# epapertagjig.net
KiCad netlist of a schematic drawn in EAGLE
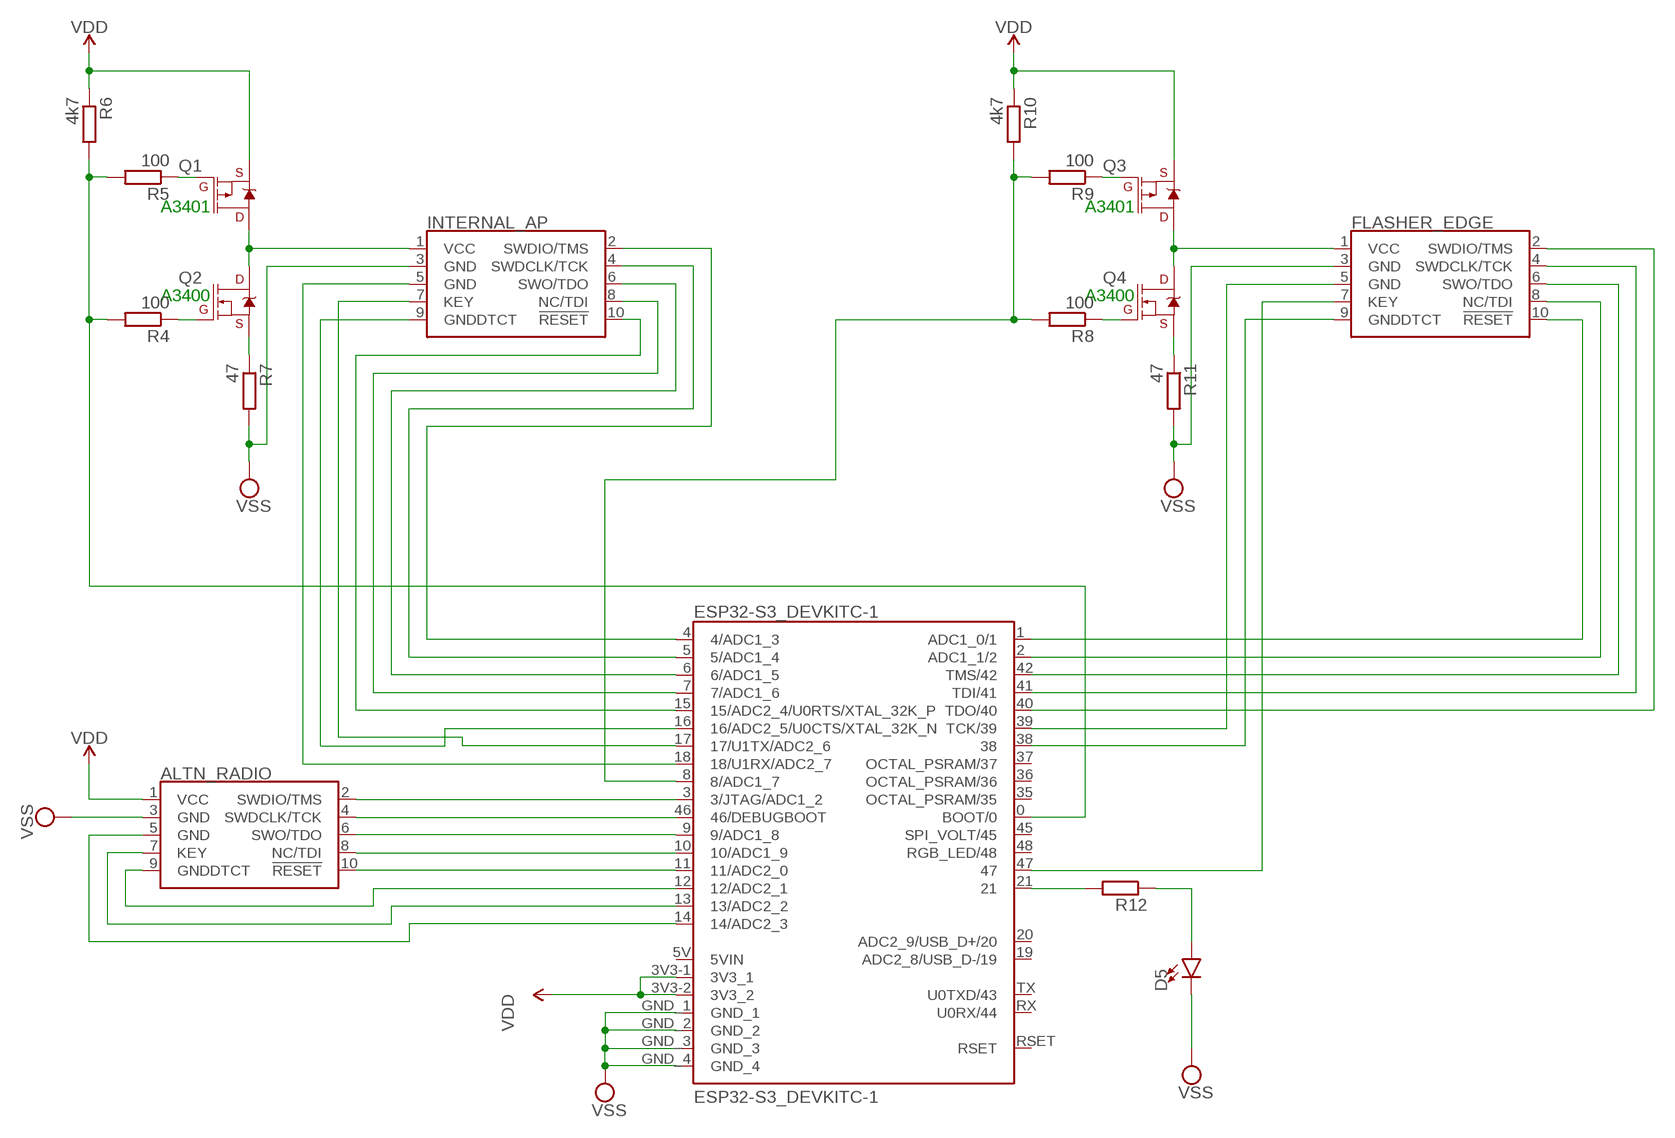
[diagram p0: schematic, sheet 1]
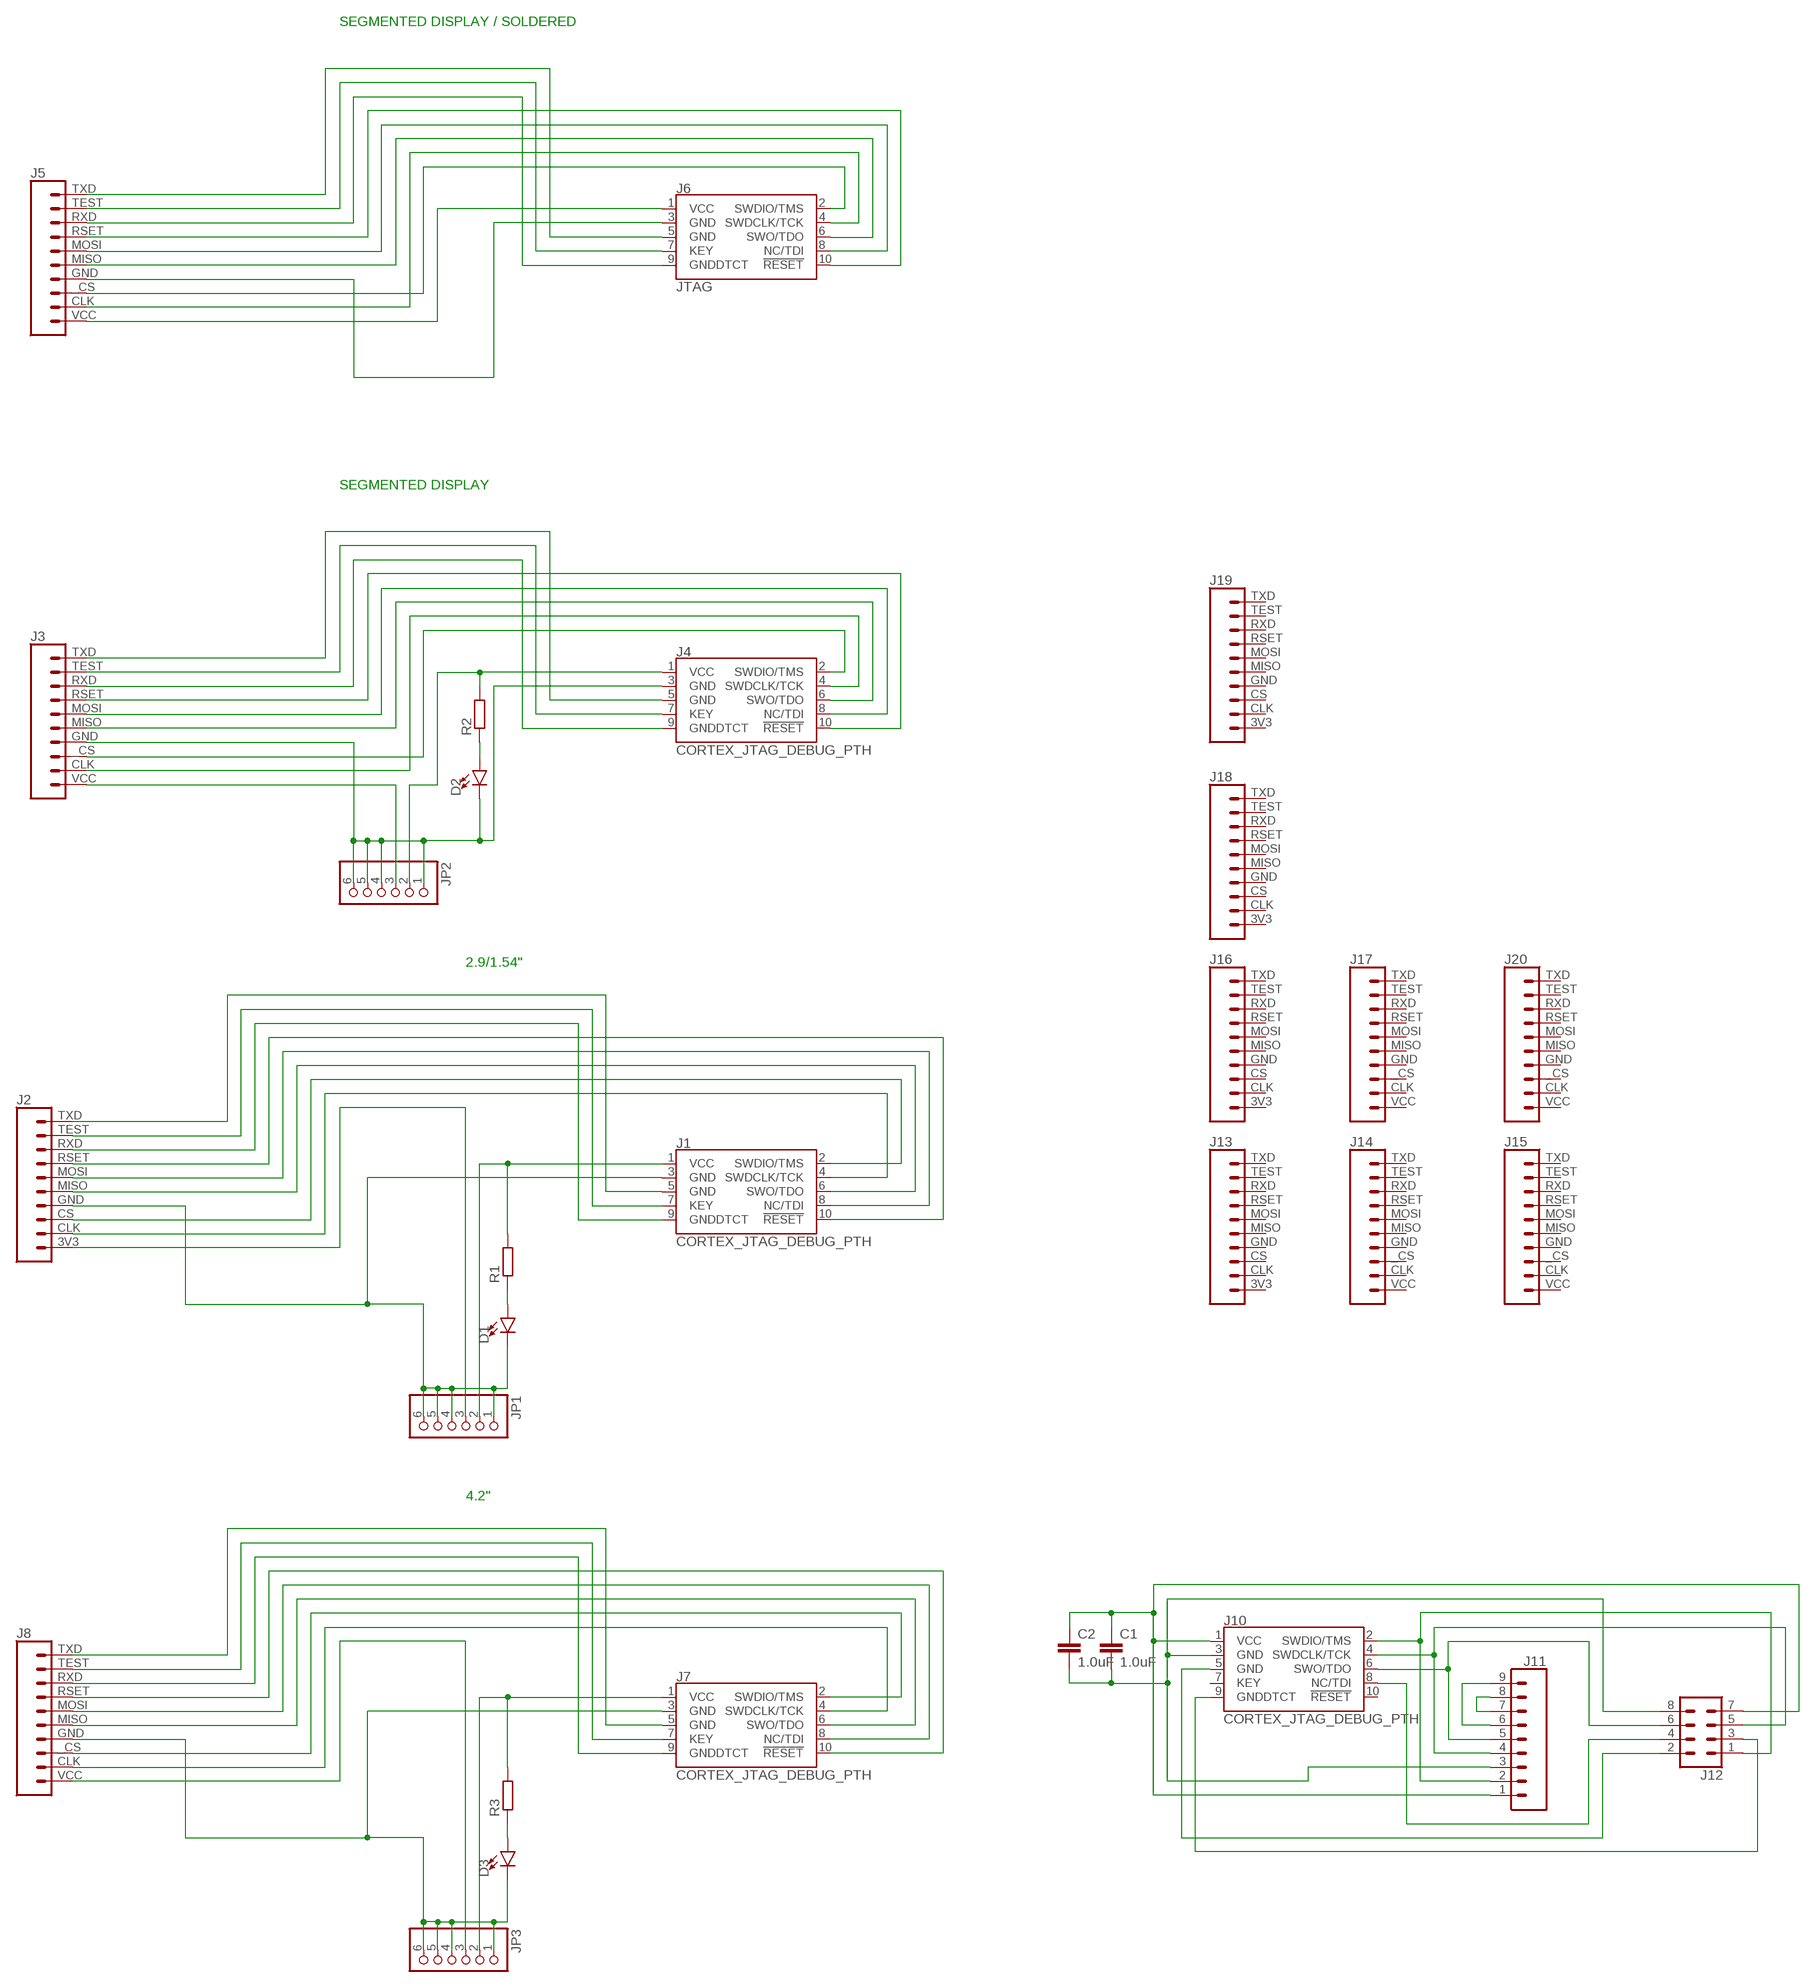
[diagram p1: schematic, sheet 2]

(export (version "E")
  (design (tool "Eeschema 10.0.6"))
  (components
    (comp (ref "C1")
      (value "1.0uF")
      (footprint "eagle-import:1206")
      (libsource (lib "eagle-import") (part "1.0UF-1206-50V-10%"))
    )
    (comp (ref "C2")
      (value "1.0uF")
      (footprint "eagle-import:1206")
      (libsource (lib "eagle-import") (part "1.0UF-1206-50V-10%"))
    )
    (comp (ref "D1")
      (value "LED1206")
      (footprint "eagle-import:LED-1206")
      (libsource (lib "eagle-import") (part "LED1206"))
    )
    (comp (ref "D2")
      (value "LED1206")
      (footprint "eagle-import:LED-1206")
      (libsource (lib "eagle-import") (part "LED1206"))
    )
    (comp (ref "D3")
      (value "LED1206")
      (footprint "eagle-import:LED-1206")
      (libsource (lib "eagle-import") (part "LED1206"))
    )
    (comp (ref "J1")
      (value "CORTEX_JTAG_DEBUG_PTH")
      (footprint "eagle-import:2X5-PTH-1.27MM")
      (libsource (lib "eagle-import") (part "CORTEX_JTAG_DEBUG_PTH"))
    )
    (comp (ref "J2")
      (value "SOLUM_ZBS_DEBUG")
      (footprint "eagle-import:SOLUM_ZBS_DEBUG")
      (libsource (lib "eagle-import") (part "SOLUM_ZBS_DEBUG"))
    )
    (comp (ref "J3")
      (value "SOLUM_ZBS_DEBUGSEGMENTED_DISPLAY")
      (footprint "eagle-import:SOLUM_ZBS_DEBUG_SEG")
      (libsource (lib "eagle-import") (part "SOLUM_ZBS_DEBUGSEGMENTED_DISPLAY"))
    )
    (comp (ref "J4")
      (value "CORTEX_JTAG_DEBUG_PTH")
      (footprint "eagle-import:2X5-PTH-1.27MM")
      (libsource (lib "eagle-import") (part "CORTEX_JTAG_DEBUG_PTH"))
    )
    (comp (ref "J5")
      (value "SOLUM_ZBS_DEBUGSEGMENTED_DISPLAY")
      (footprint "eagle-import:SOLUM_ZBS_DEBUG_SEG")
      (libsource (lib "eagle-import") (part "SOLUM_ZBS_DEBUGSEGMENTED_DISPLAY"))
    )
    (comp (ref "J6")
      (value "JTAG")
      (footprint "eagle-import:2X5-SMD-1.27MM")
      (libsource (lib "eagle-import") (part "CORTEX_JTAG_DEBUG_SMD"))
    )
    (comp (ref "J7")
      (value "CORTEX_JTAG_DEBUG_PTH")
      (footprint "eagle-import:2X5-PTH-1.27MM")
      (libsource (lib "eagle-import") (part "CORTEX_JTAG_DEBUG_PTH"))
    )
    (comp (ref "J8")
      (value "SOLUM_ZBS_DEBUGSOLUM_ZBS_DEBUG_4.2")
      (footprint "eagle-import:SOLUM_ZBS_DEBUG_4.2")
      (libsource (lib "eagle-import") (part "SOLUM_ZBS_DEBUGSOLUM_ZBS_DEBUG_4.2"))
    )
    (comp (ref "J10")
      (value "CORTEX_JTAG_DEBUG_PTH")
      (footprint "eagle-import:2X5-PTH-1.27MM")
      (libsource (lib "eagle-import") (part "CORTEX_JTAG_DEBUG_PTH"))
    )
    (comp (ref "J11")
      (value "CONN_09")
      (footprint "eagle-import:1X09")
      (libsource (lib "eagle-import") (part "CONN_09"))
    )
    (comp (ref "J12")
      (value "CONN_04X2")
      (footprint "eagle-import:2X4")
      (libsource (lib "eagle-import") (part "CONN_04X2"))
    )
    (comp (ref "J13")
      (value "SOLUM_ZBS_DEBUG")
      (footprint "eagle-import:SOLUM_ZBS_DEBUG")
      (libsource (lib "eagle-import") (part "SOLUM_ZBS_DEBUG"))
    )
    (comp (ref "J14")
      (value "SOLUM_ZBS_DEBUGSEGMENTED_DISPLAY")
      (footprint "eagle-import:SOLUM_ZBS_DEBUG_SEG")
      (libsource (lib "eagle-import") (part "SOLUM_ZBS_DEBUGSEGMENTED_DISPLAY"))
    )
    (comp (ref "J15")
      (value "SOLUM_ZBS_DEBUGSOLUM_ZBS_DEBUG_4.2")
      (footprint "eagle-import:SOLUM_ZBS_DEBUG_4.2")
      (libsource (lib "eagle-import") (part "SOLUM_ZBS_DEBUGSOLUM_ZBS_DEBUG_4.2"))
    )
    (comp (ref "J16")
      (value "SOLUM_ZBS_DEBUG")
      (footprint "eagle-import:SOLUM_ZBS_DEBUG")
      (libsource (lib "eagle-import") (part "SOLUM_ZBS_DEBUG"))
    )
    (comp (ref "J17")
      (value "SOLUM_ZBS_DEBUGSEGMENTED_DISPLAY")
      (footprint "eagle-import:SOLUM_ZBS_DEBUG_SEG")
      (libsource (lib "eagle-import") (part "SOLUM_ZBS_DEBUGSEGMENTED_DISPLAY"))
    )
    (comp (ref "J18")
      (value "SOLUM_ZBS_DEBUG")
      (footprint "eagle-import:SOLUM_ZBS_DEBUG")
      (libsource (lib "eagle-import") (part "SOLUM_ZBS_DEBUG"))
    )
    (comp (ref "J19")
      (value "SOLUM_ZBS_DEBUG")
      (footprint "eagle-import:SOLUM_ZBS_DEBUG")
      (libsource (lib "eagle-import") (part "SOLUM_ZBS_DEBUG"))
    )
    (comp (ref "J20")
      (value "SOLUM_ZBS_DEBUGSOLUM_ZBS_DEBUG_4.2")
      (footprint "eagle-import:SOLUM_ZBS_DEBUG_4.2")
      (libsource (lib "eagle-import") (part "SOLUM_ZBS_DEBUGSOLUM_ZBS_DEBUG_4.2"))
    )
    (comp (ref "JP1")
      (value "PINHD-1X6/90")
      (footprint "eagle-import:1X06_90")
      (libsource (lib "eagle-import") (part "PINHD-1X6/90"))
    )
    (comp (ref "JP2")
      (value "PINHD-1X6/90")
      (footprint "eagle-import:1X06_90")
      (libsource (lib "eagle-import") (part "PINHD-1X6/90"))
    )
    (comp (ref "JP3")
      (value "PINHD-1X6/90")
      (footprint "eagle-import:1X06_90")
      (libsource (lib "eagle-import") (part "PINHD-1X6/90"))
    )
    (comp (ref "R1")
      (value "R-EU_R1206")
      (footprint "eagle-import:R1206")
      (libsource (lib "eagle-import") (part "R-EU_R1206"))
    )
    (comp (ref "R2")
      (value "R-EU_R1206")
      (footprint "eagle-import:R1206")
      (libsource (lib "eagle-import") (part "R-EU_R1206"))
    )
    (comp (ref "R3")
      (value "R-EU_R1206")
      (footprint "eagle-import:R1206")
      (libsource (lib "eagle-import") (part "R-EU_R1206"))
    )
    (comp (ref "ALTN_RADIO")
      (value "JTAG")
      (footprint "eagle-import:2X5-SMD-1.27MM")
      (libsource (lib "eagle-import") (part "CORTEX_JTAG_DEBUG_SMD"))
    )
    (comp (ref "D5")
      (value "LED1206")
      (footprint "eagle-import:LED-1206")
      (libsource (lib "eagle-import") (part "LED1206"))
    )
    (comp (ref "FLASHER_EDGE")
      (value "CORTEX_JTAG_DEBUG_PTH")
      (footprint "eagle-import:2X5-PTH-1.27MM")
      (libsource (lib "eagle-import") (part "CORTEX_JTAG_DEBUG_PTH"))
    )
    (comp (ref "INTERNAL_AP")
      (value "JTAG")
      (footprint "eagle-import:2X5-SMD-1.27MM")
      (libsource (lib "eagle-import") (part "CORTEX_JTAG_DEBUG_SMD"))
    )
    (comp (ref "J9")
      (value "ESP32-S3_DEVKITC-1")
      (footprint "eagle-import:ESP32-S3_DEVKITC-1")
      (libsource (lib "eagle-import") (part "ESP32-S3_DEVKITC-1"))
    )
    (comp (ref "Q1")
      (value "1.1A/60V/600mΩ")
      (footprint "eagle-import:SOT23-3")
      (libsource (lib "eagle-import") (part "MOSFET_PCH-SI2309DS"))
    )
    (comp (ref "Q2")
      (value "5.8A/30V/35mΩ")
      (footprint "eagle-import:SOT23-3")
      (libsource (lib "eagle-import") (part "MOSFET-NCH-AO3404A"))
    )
    (comp (ref "Q3")
      (value "1.1A/60V/600mΩ")
      (footprint "eagle-import:SOT23-3")
      (libsource (lib "eagle-import") (part "MOSFET_PCH-SI2309DS"))
    )
    (comp (ref "Q4")
      (value "5.8A/30V/35mΩ")
      (footprint "eagle-import:SOT23-3")
      (libsource (lib "eagle-import") (part "MOSFET-NCH-AO3404A"))
    )
    (comp (ref "R4")
      (value "100")
      (footprint "eagle-import:R1206")
      (libsource (lib "eagle-import") (part "R-EU_R1206"))
    )
    (comp (ref "R5")
      (value "100")
      (footprint "eagle-import:R1206")
      (libsource (lib "eagle-import") (part "R-EU_R1206"))
    )
    (comp (ref "R6")
      (value "4k7")
      (footprint "eagle-import:R1206")
      (libsource (lib "eagle-import") (part "R-EU_R1206"))
    )
    (comp (ref "R7")
      (value "47")
      (footprint "eagle-import:R1206")
      (libsource (lib "eagle-import") (part "R-EU_R1206"))
    )
    (comp (ref "R8")
      (value "100")
      (footprint "eagle-import:R1206")
      (libsource (lib "eagle-import") (part "R-EU_R1206"))
    )
    (comp (ref "R9")
      (value "100")
      (footprint "eagle-import:R1206")
      (libsource (lib "eagle-import") (part "R-EU_R1206"))
    )
    (comp (ref "R10")
      (value "4k7")
      (footprint "eagle-import:R1206")
      (libsource (lib "eagle-import") (part "R-EU_R1206"))
    )
    (comp (ref "R11")
      (value "47")
      (footprint "eagle-import:R1206")
      (libsource (lib "eagle-import") (part "R-EU_R1206"))
    )
    (comp (ref "R12")
      (value "R-EU_R1206")
      (footprint "eagle-import:R1206")
      (libsource (lib "eagle-import") (part "R-EU_R1206"))
    )
  )
  (nets
    (net (code "1") (name "Net-(ALTN_RADIO-GNDDTCT)") (class "Default")
      (node (ref "ALTN_RADIO") (pin "9") (pinfunction "GNDDTCT_9") (pintype "bidirectional"))
      (node (ref "J9") (pin "12") (pinfunction "12/ADC2_1_12") (pintype "bidirectional"))
    )
    (net (code "2") (name "Net-(ALTN_RADIO-KEY)") (class "Default")
      (node (ref "ALTN_RADIO") (pin "7") (pinfunction "KEY_7") (pintype "bidirectional"))
      (node (ref "J9") (pin "13") (pinfunction "13/ADC2_2_13") (pintype "bidirectional"))
    )
    (net (code "3") (name "Net-(ALTN_RADIO-NC{slash}TDI)") (class "Default")
      (node (ref "ALTN_RADIO") (pin "8") (pinfunction "NC/TDI_8") (pintype "bidirectional"))
      (node (ref "J9") (pin "10") (pinfunction "10/ADC1_9_10") (pintype "bidirectional"))
    )
    (net (code "4") (name "Net-(ALTN_RADIO-SWDCLK{slash}TCK)") (class "Default")
      (node (ref "ALTN_RADIO") (pin "4") (pinfunction "SWDCLK/TCK_4") (pintype "bidirectional"))
      (node (ref "J9") (pin "46") (pinfunction "46/DEBUGBOOT_46") (pintype "bidirectional"))
    )
    (net (code "5") (name "Net-(ALTN_RADIO-SWDIO{slash}TMS)") (class "Default")
      (node (ref "ALTN_RADIO") (pin "2") (pinfunction "SWDIO/TMS_2") (pintype "bidirectional"))
      (node (ref "J9") (pin "3") (pinfunction "3/JTAG/ADC1_2_3") (pintype "bidirectional"))
    )
    (net (code "6") (name "Net-(ALTN_RADIO-SWO{slash}TDO)") (class "Default")
      (node (ref "ALTN_RADIO") (pin "6") (pinfunction "SWO/TDO_6") (pintype "bidirectional"))
      (node (ref "J9") (pin "9") (pinfunction "9/ADC1_8_9") (pintype "bidirectional"))
    )
    (net (code "7") (name "Net-(ALTN_RADIO-~{RESET})") (class "Default")
      (node (ref "ALTN_RADIO") (pin "10") (pinfunction "~{RESET}_10") (pintype "bidirectional"))
      (node (ref "J9") (pin "11") (pinfunction "11/ADC2_0_11") (pintype "bidirectional"))
    )
    (net (code "8") (name "Net-(C1-Pad2)") (class "Default")
      (node (ref "C1") (pin "2") (pinfunction "2_2") (pintype "passive"))
      (node (ref "C2") (pin "2") (pinfunction "2_2") (pintype "passive"))
      (node (ref "J10") (pin "3") (pinfunction "GND_3") (pintype "bidirectional"))
      (node (ref "J11") (pin "3") (pinfunction "3_3") (pintype "passive"))
      (node (ref "J12") (pin "8") (pinfunction "8_8") (pintype "passive"))
    )
    (net (code "9") (name "Net-(D1-PadA)") (class "Default")
      (node (ref "D1") (pin "A") (pinfunction "A_A") (pintype "passive"))
      (node (ref "R1") (pin "1") (pinfunction "1_1") (pintype "passive"))
    )
    (net (code "10") (name "Net-(D2-PadA)") (class "Default")
      (node (ref "D2") (pin "A") (pinfunction "A_A") (pintype "passive"))
      (node (ref "R2") (pin "1") (pinfunction "1_1") (pintype "passive"))
    )
    (net (code "11") (name "Net-(D3-PadA)") (class "Default")
      (node (ref "D3") (pin "A") (pinfunction "A_A") (pintype "passive"))
      (node (ref "R3") (pin "1") (pinfunction "1_1") (pintype "passive"))
    )
    (net (code "12") (name "Net-(D5-PadA)") (class "Default")
      (node (ref "D5") (pin "A") (pinfunction "A_A") (pintype "passive"))
      (node (ref "R12") (pin "1") (pinfunction "1_1") (pintype "passive"))
    )
    (net (code "13") (name "Net-(FLASHER_EDGE-GNDDTCT)") (class "Default")
      (node (ref "FLASHER_EDGE") (pin "9") (pinfunction "GNDDTCT_9") (pintype "bidirectional"))
      (node (ref "J9") (pin "38") (pinfunction "38_38") (pintype "bidirectional"))
    )
    (net (code "14") (name "Net-(FLASHER_EDGE-KEY)") (class "Default")
      (node (ref "FLASHER_EDGE") (pin "7") (pinfunction "KEY_7") (pintype "bidirectional"))
      (node (ref "J9") (pin "47") (pinfunction "47_47") (pintype "bidirectional"))
    )
    (net (code "15") (name "Net-(FLASHER_EDGE-NC{slash}TDI)") (class "Default")
      (node (ref "FLASHER_EDGE") (pin "8") (pinfunction "NC/TDI_8") (pintype "bidirectional"))
      (node (ref "J9") (pin "2") (pinfunction "ADC1_1/2_2") (pintype "bidirectional"))
    )
    (net (code "16") (name "Net-(FLASHER_EDGE-SWDCLK{slash}TCK)") (class "Default")
      (node (ref "FLASHER_EDGE") (pin "4") (pinfunction "SWDCLK/TCK_4") (pintype "bidirectional"))
      (node (ref "J9") (pin "41") (pinfunction "TDI/41_41") (pintype "bidirectional"))
    )
    (net (code "17") (name "Net-(FLASHER_EDGE-SWDIO{slash}TMS)") (class "Default")
      (node (ref "FLASHER_EDGE") (pin "2") (pinfunction "SWDIO/TMS_2") (pintype "bidirectional"))
      (node (ref "J9") (pin "40") (pinfunction "TDO/40_40") (pintype "bidirectional"))
    )
    (net (code "18") (name "Net-(FLASHER_EDGE-SWO{slash}TDO)") (class "Default")
      (node (ref "FLASHER_EDGE") (pin "6") (pinfunction "SWO/TDO_6") (pintype "bidirectional"))
      (node (ref "J9") (pin "42") (pinfunction "TMS/42_42") (pintype "bidirectional"))
    )
    (net (code "19") (name "Net-(FLASHER_EDGE-VCC)") (class "Default")
      (node (ref "FLASHER_EDGE") (pin "1") (pinfunction "VCC_1") (pintype "bidirectional"))
      (node (ref "Q3") (pin "3") (pinfunction "D_3") (pintype "bidirectional"))
      (node (ref "Q4") (pin "3") (pinfunction "D_3") (pintype "bidirectional"))
    )
    (net (code "20") (name "Net-(FLASHER_EDGE-~{RESET})") (class "Default")
      (node (ref "FLASHER_EDGE") (pin "10") (pinfunction "~{RESET}_10") (pintype "bidirectional"))
      (node (ref "J9") (pin "1") (pinfunction "ADC1_0/1_1") (pintype "bidirectional"))
    )
    (net (code "21") (name "Net-(INTERNAL_AP-GNDDTCT)") (class "Default")
      (node (ref "INTERNAL_AP") (pin "9") (pinfunction "GNDDTCT_9") (pintype "bidirectional"))
      (node (ref "J9") (pin "16") (pinfunction "16/ADC2_5/U0CTS/XTAL_32K_N_16") (pintype "bidirectional"))
    )
    (net (code "22") (name "Net-(INTERNAL_AP-KEY)") (class "Default")
      (node (ref "INTERNAL_AP") (pin "7") (pinfunction "KEY_7") (pintype "bidirectional"))
      (node (ref "J9") (pin "17") (pinfunction "17/U1TX/ADC2_6_17") (pintype "bidirectional"))
    )
    (net (code "23") (name "Net-(INTERNAL_AP-NC{slash}TDI)") (class "Default")
      (node (ref "INTERNAL_AP") (pin "8") (pinfunction "NC/TDI_8") (pintype "bidirectional"))
      (node (ref "J9") (pin "7") (pinfunction "7/ADC1_6_7") (pintype "bidirectional"))
    )
    (net (code "24") (name "Net-(INTERNAL_AP-SWDCLK{slash}TCK)") (class "Default")
      (node (ref "INTERNAL_AP") (pin "4") (pinfunction "SWDCLK/TCK_4") (pintype "bidirectional"))
      (node (ref "J9") (pin "5") (pinfunction "5/ADC1_4_5") (pintype "bidirectional"))
    )
    (net (code "25") (name "Net-(INTERNAL_AP-SWDIO{slash}TMS)") (class "Default")
      (node (ref "INTERNAL_AP") (pin "2") (pinfunction "SWDIO/TMS_2") (pintype "bidirectional"))
      (node (ref "J9") (pin "4") (pinfunction "4/ADC1_3_4") (pintype "bidirectional"))
    )
    (net (code "26") (name "Net-(INTERNAL_AP-SWO{slash}TDO)") (class "Default")
      (node (ref "INTERNAL_AP") (pin "6") (pinfunction "SWO/TDO_6") (pintype "bidirectional"))
      (node (ref "J9") (pin "6") (pinfunction "6/ADC1_5_6") (pintype "bidirectional"))
    )
    (net (code "27") (name "Net-(INTERNAL_AP-VCC)") (class "Default")
      (node (ref "INTERNAL_AP") (pin "1") (pinfunction "VCC_1") (pintype "bidirectional"))
      (node (ref "Q1") (pin "3") (pinfunction "D_3") (pintype "bidirectional"))
      (node (ref "Q2") (pin "3") (pinfunction "D_3") (pintype "bidirectional"))
    )
    (net (code "28") (name "Net-(INTERNAL_AP-~{RESET})") (class "Default")
      (node (ref "INTERNAL_AP") (pin "10") (pinfunction "~{RESET}_10") (pintype "bidirectional"))
      (node (ref "J9") (pin "15") (pinfunction "15/ADC2_4/U0RTS/XTAL_32K_P_15") (pintype "bidirectional"))
    )
    (net (code "29") (name "Net-(J1-GNDDTCT)") (class "Default")
      (node (ref "J1") (pin "9") (pinfunction "GNDDTCT_9") (pintype "bidirectional"))
      (node (ref "J2") (pin "RXD") (pinfunction "8_RXD") (pintype "passive"))
    )
    (net (code "30") (name "Net-(J1-KEY)") (class "Default")
      (node (ref "J1") (pin "7") (pinfunction "KEY_7") (pintype "bidirectional"))
      (node (ref "J2") (pin "TEST") (pinfunction "9_TEST") (pintype "passive"))
    )
    (net (code "31") (name "Net-(J1-NC{slash}TDI)") (class "Default")
      (node (ref "J1") (pin "8") (pinfunction "NC/TDI_8") (pintype "bidirectional"))
      (node (ref "J2") (pin "MOSI") (pinfunction "6_MOSI") (pintype "passive"))
    )
    (net (code "32") (name "Net-(J1-SWDCLK{slash}TCK)") (class "Default")
      (node (ref "J1") (pin "4") (pinfunction "SWDCLK/TCK_4") (pintype "bidirectional"))
      (node (ref "J2") (pin "CLK") (pinfunction "2_CLK") (pintype "passive"))
    )
    (net (code "33") (name "Net-(J1-SWDIO{slash}TMS)") (class "Default")
      (node (ref "J1") (pin "2") (pinfunction "SWDIO/TMS_2") (pintype "bidirectional"))
      (node (ref "J2") (pin "CS") (pinfunction "3_CS") (pintype "passive"))
    )
    (net (code "34") (name "Net-(J1-SWO{slash}TDO)") (class "Default")
      (node (ref "J1") (pin "6") (pinfunction "SWO/TDO_6") (pintype "bidirectional"))
      (node (ref "J2") (pin "MISO") (pinfunction "5_MISO") (pintype "passive"))
    )
    (net (code "35") (name "Net-(J1-VCC)") (class "Default")
      (node (ref "J1") (pin "1") (pinfunction "VCC_1") (pintype "bidirectional"))
      (node (ref "JP1") (pin "2") (pinfunction "2_2") (pintype "passive"))
      (node (ref "R1") (pin "2") (pinfunction "2_2") (pintype "passive"))
    )
    (net (code "36") (name "Net-(J1-~{RESET})") (class "Default")
      (node (ref "J1") (pin "10") (pinfunction "~{RESET}_10") (pintype "bidirectional"))
      (node (ref "J2") (pin "RSET") (pinfunction "7_RSET") (pintype "passive"))
    )
    (net (code "37") (name "Net-(J2-1)") (class "Default")
      (node (ref "J2") (pin "3V3") (pinfunction "1_3V3") (pintype "passive"))
      (node (ref "JP1") (pin "3") (pinfunction "3_3") (pintype "passive"))
    )
    (net (code "38") (name "Net-(J2-4)") (class "Default")
      (node (ref "D1") (pin "C") (pinfunction "C_C") (pintype "passive"))
      (node (ref "J1") (pin "3") (pinfunction "GND_3") (pintype "bidirectional"))
      (node (ref "J2") (pin "GND") (pinfunction "4_GND") (pintype "passive"))
      (node (ref "JP1") (pin "1") (pinfunction "1_1") (pintype "passive"))
      (node (ref "JP1") (pin "4") (pinfunction "4_4") (pintype "passive"))
      (node (ref "JP1") (pin "5") (pinfunction "5_5") (pintype "passive"))
      (node (ref "JP1") (pin "6") (pinfunction "6_6") (pintype "passive"))
    )
    (net (code "39") (name "Net-(J2-10)") (class "Default")
      (node (ref "J1") (pin "5") (pinfunction "GND_5") (pintype "bidirectional"))
      (node (ref "J2") (pin "TXD") (pinfunction "10_TXD") (pintype "passive"))
    )
    (net (code "40") (name "Net-(J3-1)") (class "Default")
      (node (ref "J3") (pin "VCC") (pinfunction "1_VCC") (pintype "passive"))
      (node (ref "JP2") (pin "3") (pinfunction "3_3") (pintype "passive"))
    )
    (net (code "41") (name "Net-(J3-2)") (class "Default")
      (node (ref "J3") (pin "CLK") (pinfunction "2_CLK") (pintype "passive"))
      (node (ref "J4") (pin "4") (pinfunction "SWDCLK/TCK_4") (pintype "bidirectional"))
    )
    (net (code "42") (name "Net-(J3-3)") (class "Default")
      (node (ref "J3") (pin "_CS") (pinfunction "3__CS") (pintype "passive"))
      (node (ref "J4") (pin "2") (pinfunction "SWDIO/TMS_2") (pintype "bidirectional"))
    )
    (net (code "43") (name "Net-(J3-4)") (class "Default")
      (node (ref "D2") (pin "C") (pinfunction "C_C") (pintype "passive"))
      (node (ref "J3") (pin "GND") (pinfunction "4_GND") (pintype "passive"))
      (node (ref "J4") (pin "3") (pinfunction "GND_3") (pintype "bidirectional"))
      (node (ref "JP2") (pin "1") (pinfunction "1_1") (pintype "passive"))
      (node (ref "JP2") (pin "4") (pinfunction "4_4") (pintype "passive"))
      (node (ref "JP2") (pin "5") (pinfunction "5_5") (pintype "passive"))
      (node (ref "JP2") (pin "6") (pinfunction "6_6") (pintype "passive"))
    )
    (net (code "44") (name "Net-(J3-5)") (class "Default")
      (node (ref "J3") (pin "MISO") (pinfunction "5_MISO") (pintype "passive"))
      (node (ref "J4") (pin "6") (pinfunction "SWO/TDO_6") (pintype "bidirectional"))
    )
    (net (code "45") (name "Net-(J3-6)") (class "Default")
      (node (ref "J3") (pin "MOSI") (pinfunction "6_MOSI") (pintype "passive"))
      (node (ref "J4") (pin "8") (pinfunction "NC/TDI_8") (pintype "bidirectional"))
    )
    (net (code "46") (name "Net-(J3-7)") (class "Default")
      (node (ref "J3") (pin "RSET") (pinfunction "7_RSET") (pintype "passive"))
      (node (ref "J4") (pin "10") (pinfunction "~{RESET}_10") (pintype "bidirectional"))
    )
    (net (code "47") (name "Net-(J3-8)") (class "Default")
      (node (ref "J3") (pin "RXD") (pinfunction "8_RXD") (pintype "passive"))
      (node (ref "J4") (pin "9") (pinfunction "GNDDTCT_9") (pintype "bidirectional"))
    )
    (net (code "48") (name "Net-(J3-9)") (class "Default")
      (node (ref "J3") (pin "TEST") (pinfunction "9_TEST") (pintype "passive"))
      (node (ref "J4") (pin "7") (pinfunction "KEY_7") (pintype "bidirectional"))
    )
    (net (code "49") (name "Net-(J3-10)") (class "Default")
      (node (ref "J3") (pin "TXD") (pinfunction "10_TXD") (pintype "passive"))
      (node (ref "J4") (pin "5") (pinfunction "GND_5") (pintype "bidirectional"))
    )
    (net (code "50") (name "Net-(J4-VCC)") (class "Default")
      (node (ref "J4") (pin "1") (pinfunction "VCC_1") (pintype "bidirectional"))
      (node (ref "JP2") (pin "2") (pinfunction "2_2") (pintype "passive"))
      (node (ref "R2") (pin "2") (pinfunction "2_2") (pintype "passive"))
    )
    (net (code "51") (name "Net-(J5-1)") (class "Default")
      (node (ref "J5") (pin "VCC") (pinfunction "1_VCC") (pintype "passive"))
      (node (ref "J6") (pin "1") (pinfunction "VCC_1") (pintype "bidirectional"))
    )
    (net (code "52") (name "Net-(J5-2)") (class "Default")
      (node (ref "J5") (pin "CLK") (pinfunction "2_CLK") (pintype "passive"))
      (node (ref "J6") (pin "4") (pinfunction "SWDCLK/TCK_4") (pintype "bidirectional"))
    )
    (net (code "53") (name "Net-(J5-3)") (class "Default")
      (node (ref "J5") (pin "_CS") (pinfunction "3__CS") (pintype "passive"))
      (node (ref "J6") (pin "2") (pinfunction "SWDIO/TMS_2") (pintype "bidirectional"))
    )
    (net (code "54") (name "Net-(J5-4)") (class "Default")
      (node (ref "J5") (pin "GND") (pinfunction "4_GND") (pintype "passive"))
      (node (ref "J6") (pin "3") (pinfunction "GND_3") (pintype "bidirectional"))
    )
    (net (code "55") (name "Net-(J5-5)") (class "Default")
      (node (ref "J5") (pin "MISO") (pinfunction "5_MISO") (pintype "passive"))
      (node (ref "J6") (pin "6") (pinfunction "SWO/TDO_6") (pintype "bidirectional"))
    )
    (net (code "56") (name "Net-(J5-6)") (class "Default")
      (node (ref "J5") (pin "MOSI") (pinfunction "6_MOSI") (pintype "passive"))
      (node (ref "J6") (pin "8") (pinfunction "NC/TDI_8") (pintype "bidirectional"))
    )
    (net (code "57") (name "Net-(J5-7)") (class "Default")
      (node (ref "J5") (pin "RSET") (pinfunction "7_RSET") (pintype "passive"))
      (node (ref "J6") (pin "10") (pinfunction "~{RESET}_10") (pintype "bidirectional"))
    )
    (net (code "58") (name "Net-(J5-8)") (class "Default")
      (node (ref "J5") (pin "RXD") (pinfunction "8_RXD") (pintype "passive"))
      (node (ref "J6") (pin "9") (pinfunction "GNDDTCT_9") (pintype "bidirectional"))
    )
    (net (code "59") (name "Net-(J5-9)") (class "Default")
      (node (ref "J5") (pin "TEST") (pinfunction "9_TEST") (pintype "passive"))
      (node (ref "J6") (pin "7") (pinfunction "KEY_7") (pintype "bidirectional"))
    )
    (net (code "60") (name "Net-(J5-10)") (class "Default")
      (node (ref "J5") (pin "TXD") (pinfunction "10_TXD") (pintype "passive"))
      (node (ref "J6") (pin "5") (pinfunction "GND_5") (pintype "bidirectional"))
    )
    (net (code "61") (name "Net-(J7-GNDDTCT)") (class "Default")
      (node (ref "J7") (pin "9") (pinfunction "GNDDTCT_9") (pintype "bidirectional"))
      (node (ref "J8") (pin "RXD") (pinfunction "8_RXD") (pintype "passive"))
    )
    (net (code "62") (name "Net-(J7-KEY)") (class "Default")
      (node (ref "J7") (pin "7") (pinfunction "KEY_7") (pintype "bidirectional"))
      (node (ref "J8") (pin "TEST") (pinfunction "9_TEST") (pintype "passive"))
    )
    (net (code "63") (name "Net-(J7-NC{slash}TDI)") (class "Default")
      (node (ref "J7") (pin "8") (pinfunction "NC/TDI_8") (pintype "bidirectional"))
      (node (ref "J8") (pin "MOSI") (pinfunction "6_MOSI") (pintype "passive"))
    )
    (net (code "64") (name "Net-(J7-SWDCLK{slash}TCK)") (class "Default")
      (node (ref "J7") (pin "4") (pinfunction "SWDCLK/TCK_4") (pintype "bidirectional"))
      (node (ref "J8") (pin "CLK") (pinfunction "2_CLK") (pintype "passive"))
    )
    (net (code "65") (name "Net-(J7-SWDIO{slash}TMS)") (class "Default")
      (node (ref "J7") (pin "2") (pinfunction "SWDIO/TMS_2") (pintype "bidirectional"))
      (node (ref "J8") (pin "_CS") (pinfunction "3__CS") (pintype "passive"))
    )
    (net (code "66") (name "Net-(J7-SWO{slash}TDO)") (class "Default")
      (node (ref "J7") (pin "6") (pinfunction "SWO/TDO_6") (pintype "bidirectional"))
      (node (ref "J8") (pin "MISO") (pinfunction "5_MISO") (pintype "passive"))
    )
    (net (code "67") (name "Net-(J7-VCC)") (class "Default")
      (node (ref "J7") (pin "1") (pinfunction "VCC_1") (pintype "bidirectional"))
      (node (ref "JP3") (pin "2") (pinfunction "2_2") (pintype "passive"))
      (node (ref "R3") (pin "2") (pinfunction "2_2") (pintype "passive"))
    )
    (net (code "68") (name "Net-(J7-~{RESET})") (class "Default")
      (node (ref "J7") (pin "10") (pinfunction "~{RESET}_10") (pintype "bidirectional"))
      (node (ref "J8") (pin "RSET") (pinfunction "7_RSET") (pintype "passive"))
    )
    (net (code "69") (name "Net-(J8-1)") (class "Default")
      (node (ref "J8") (pin "VCC") (pinfunction "1_VCC") (pintype "passive"))
      (node (ref "JP3") (pin "3") (pinfunction "3_3") (pintype "passive"))
    )
    (net (code "70") (name "Net-(J8-4)") (class "Default")
      (node (ref "D3") (pin "C") (pinfunction "C_C") (pintype "passive"))
      (node (ref "J7") (pin "3") (pinfunction "GND_3") (pintype "bidirectional"))
      (node (ref "J8") (pin "GND") (pinfunction "4_GND") (pintype "passive"))
      (node (ref "JP3") (pin "1") (pinfunction "1_1") (pintype "passive"))
      (node (ref "JP3") (pin "4") (pinfunction "4_4") (pintype "passive"))
      (node (ref "JP3") (pin "5") (pinfunction "5_5") (pintype "passive"))
      (node (ref "JP3") (pin "6") (pinfunction "6_6") (pintype "passive"))
    )
    (net (code "71") (name "Net-(J8-10)") (class "Default")
      (node (ref "J7") (pin "5") (pinfunction "GND_5") (pintype "bidirectional"))
      (node (ref "J8") (pin "TXD") (pinfunction "10_TXD") (pintype "passive"))
    )
    (net (code "72") (name "Net-(J9-8{slash}ADC1_7)") (class "Default")
      (node (ref "J9") (pin "8") (pinfunction "8/ADC1_7_8") (pintype "bidirectional"))
      (node (ref "R10") (pin "2") (pinfunction "2_2") (pintype "passive"))
      (node (ref "R8") (pin "2") (pinfunction "2_2") (pintype "passive"))
      (node (ref "R9") (pin "2") (pinfunction "2_2") (pintype "passive"))
    )
    (net (code "73") (name "Net-(J9-14{slash}ADC2_3)") (class "Default")
      (node (ref "ALTN_RADIO") (pin "5") (pinfunction "GND_5") (pintype "bidirectional"))
      (node (ref "J9") (pin "14") (pinfunction "14/ADC2_3_14") (pintype "bidirectional"))
    )
    (net (code "74") (name "Net-(J9-18{slash}U1RX{slash}ADC2_7)") (class "Default")
      (node (ref "INTERNAL_AP") (pin "5") (pinfunction "GND_5") (pintype "bidirectional"))
      (node (ref "J9") (pin "18") (pinfunction "18/U1RX/ADC2_7_18") (pintype "bidirectional"))
    )
    (net (code "75") (name "Net-(J9-BOOT{slash}0)") (class "Default")
      (node (ref "J9") (pin "0") (pinfunction "BOOT/0_0") (pintype "bidirectional"))
      (node (ref "R4") (pin "2") (pinfunction "2_2") (pintype "passive"))
      (node (ref "R5") (pin "2") (pinfunction "2_2") (pintype "passive"))
      (node (ref "R6") (pin "2") (pinfunction "2_2") (pintype "passive"))
    )
    (net (code "76") (name "Net-(J9-Pad21)") (class "Default")
      (node (ref "J9") (pin "21") (pinfunction "21_21") (pintype "bidirectional"))
      (node (ref "R12") (pin "2") (pinfunction "2_2") (pintype "passive"))
    )
    (net (code "77") (name "Net-(J9-TCK{slash}39)") (class "Default")
      (node (ref "FLASHER_EDGE") (pin "5") (pinfunction "GND_5") (pintype "bidirectional"))
      (node (ref "J9") (pin "39") (pinfunction "TCK/39_39") (pintype "bidirectional"))
    )
    (net (code "78") (name "Net-(J10-GND-Pad5)") (class "Default")
      (node (ref "J10") (pin "5") (pinfunction "GND_5") (pintype "bidirectional"))
      (node (ref "J12") (pin "2") (pinfunction "2_2") (pintype "passive"))
    )
    (net (code "79") (name "Net-(J10-GNDDTCT)") (class "Default")
      (node (ref "J10") (pin "9") (pinfunction "GNDDTCT_9") (pintype "bidirectional"))
      (node (ref "J12") (pin "3") (pinfunction "3_3") (pintype "passive"))
    )
    (net (code "80") (name "Net-(J10-NC{slash}TDI)") (class "Default")
      (node (ref "J10") (pin "8") (pinfunction "NC/TDI_8") (pintype "bidirectional"))
      (node (ref "J12") (pin "4") (pinfunction "4_4") (pintype "passive"))
    )
    (net (code "81") (name "Net-(J10-SWDCLK{slash}TCK)") (class "Default")
      (node (ref "J10") (pin "4") (pinfunction "SWDCLK/TCK_4") (pintype "bidirectional"))
      (node (ref "J11") (pin "4") (pinfunction "4_4") (pintype "passive"))
      (node (ref "J12") (pin "5") (pinfunction "5_5") (pintype "passive"))
    )
    (net (code "82") (name "Net-(J10-SWDIO{slash}TMS)") (class "Default")
      (node (ref "J10") (pin "2") (pinfunction "SWDIO/TMS_2") (pintype "bidirectional"))
      (node (ref "J11") (pin "2") (pinfunction "2_2") (pintype "passive"))
      (node (ref "J12") (pin "1") (pinfunction "1_1") (pintype "passive"))
    )
    (net (code "83") (name "Net-(J10-SWO{slash}TDO)") (class "Default")
      (node (ref "J10") (pin "6") (pinfunction "SWO/TDO_6") (pintype "bidirectional"))
      (node (ref "J11") (pin "5") (pinfunction "5_5") (pintype "passive"))
      (node (ref "J12") (pin "6") (pinfunction "6_6") (pintype "passive"))
    )
    (net (code "84") (name "Net-(J10-VCC)") (class "Default")
      (node (ref "C1") (pin "1") (pinfunction "1_1") (pintype "passive"))
      (node (ref "C2") (pin "1") (pinfunction "1_1") (pintype "passive"))
      (node (ref "J10") (pin "1") (pinfunction "VCC_1") (pintype "bidirectional"))
      (node (ref "J11") (pin "1") (pinfunction "1_1") (pintype "passive"))
      (node (ref "J12") (pin "7") (pinfunction "7_7") (pintype "passive"))
    )
    (net (code "85") (name "Net-(J11-Pad6)") (class "Default")
      (node (ref "J11") (pin "6") (pinfunction "6_6") (pintype "passive"))
      (node (ref "J11") (pin "9") (pinfunction "9_9") (pintype "passive"))
    )
    (net (code "86") (name "Net-(J11-Pad7)") (class "Default")
      (node (ref "J11") (pin "7") (pinfunction "7_7") (pintype "passive"))
      (node (ref "J11") (pin "8") (pinfunction "8_8") (pintype "passive"))
    )
    (net (code "87") (name "Net-(Q1-G)") (class "Default")
      (node (ref "Q1") (pin "1") (pinfunction "G_1") (pintype "bidirectional"))
      (node (ref "R5") (pin "1") (pinfunction "1_1") (pintype "passive"))
    )
    (net (code "88") (name "Net-(Q2-G)") (class "Default")
      (node (ref "Q2") (pin "1") (pinfunction "G_1") (pintype "bidirectional"))
      (node (ref "R4") (pin "1") (pinfunction "1_1") (pintype "passive"))
    )
    (net (code "89") (name "Net-(Q2-S)") (class "Default")
      (node (ref "Q2") (pin "2") (pinfunction "S_2") (pintype "bidirectional"))
      (node (ref "R7") (pin "1") (pinfunction "1_1") (pintype "passive"))
    )
    (net (code "90") (name "Net-(Q3-G)") (class "Default")
      (node (ref "Q3") (pin "1") (pinfunction "G_1") (pintype "bidirectional"))
      (node (ref "R9") (pin "1") (pinfunction "1_1") (pintype "passive"))
    )
    (net (code "91") (name "Net-(Q4-G)") (class "Default")
      (node (ref "Q4") (pin "1") (pinfunction "G_1") (pintype "bidirectional"))
      (node (ref "R8") (pin "1") (pinfunction "1_1") (pintype "passive"))
    )
    (net (code "92") (name "Net-(Q4-S)") (class "Default")
      (node (ref "Q4") (pin "2") (pinfunction "S_2") (pintype "bidirectional"))
      (node (ref "R11") (pin "1") (pinfunction "1_1") (pintype "passive"))
    )
    (net (code "93") (name "VDD") (class "Default")
      (node (ref "ALTN_RADIO") (pin "1") (pinfunction "VCC_1") (pintype "bidirectional"))
      (node (ref "J9") (pin "3V3-1") (pinfunction "3V3_1_3V3-1") (pintype "bidirectional"))
      (node (ref "J9") (pin "3V3-2") (pinfunction "3V3_2_3V3-2") (pintype "bidirectional"))
      (node (ref "Q1") (pin "2") (pinfunction "S_2") (pintype "bidirectional"))
      (node (ref "Q3") (pin "2") (pinfunction "S_2") (pintype "bidirectional"))
      (node (ref "R10") (pin "1") (pinfunction "1_1") (pintype "passive"))
      (node (ref "R6") (pin "1") (pinfunction "1_1") (pintype "passive"))
    )
    (net (code "94") (name "VSS") (class "Default")
      (node (ref "ALTN_RADIO") (pin "3") (pinfunction "GND_3") (pintype "bidirectional"))
      (node (ref "D5") (pin "C") (pinfunction "C_C") (pintype "passive"))
      (node (ref "FLASHER_EDGE") (pin "3") (pinfunction "GND_3") (pintype "bidirectional"))
      (node (ref "INTERNAL_AP") (pin "3") (pinfunction "GND_3") (pintype "bidirectional"))
      (node (ref "J9") (pin "GND_1") (pinfunction "GND_1_GND_1") (pintype "bidirectional"))
      (node (ref "J9") (pin "GND_2") (pinfunction "GND_2_GND_2") (pintype "bidirectional"))
      (node (ref "J9") (pin "GND_3") (pinfunction "GND_3_GND_3") (pintype "bidirectional"))
      (node (ref "J9") (pin "GND_4") (pinfunction "GND_4_GND_4") (pintype "bidirectional"))
      (node (ref "R11") (pin "2") (pinfunction "2_2") (pintype "passive"))
      (node (ref "R7") (pin "2") (pinfunction "2_2") (pintype "passive"))
    )
    (net (code "95") (name "unconnected-(J9-5VIN-Pad5V)") (class "Default")
      (node (ref "J9") (pin "5V") (pinfunction "5VIN_5V") (pintype "bidirectional"))
    )
    (net (code "96") (name "unconnected-(J9-ADC2_8{slash}USB_D-{slash}19-Pad19)") (class "Default")
      (node (ref "J9") (pin "19") (pinfunction "ADC2_8/USB_D-/19_19") (pintype "bidirectional"))
    )
    (net (code "97") (name "unconnected-(J9-ADC2_9{slash}USB_D+{slash}20-Pad20)") (class "Default")
      (node (ref "J9") (pin "20") (pinfunction "ADC2_9/USB_D+/20_20") (pintype "bidirectional"))
    )
    (net (code "98") (name "unconnected-(J9-OCTAL_PSRAM{slash}35-Pad35)") (class "Default")
      (node (ref "J9") (pin "35") (pinfunction "OCTAL_PSRAM/35_35") (pintype "bidirectional"))
    )
    (net (code "99") (name "unconnected-(J9-OCTAL_PSRAM{slash}36-Pad36)") (class "Default")
      (node (ref "J9") (pin "36") (pinfunction "OCTAL_PSRAM/36_36") (pintype "bidirectional"))
    )
    (net (code "100") (name "unconnected-(J9-OCTAL_PSRAM{slash}37-Pad37)") (class "Default")
      (node (ref "J9") (pin "37") (pinfunction "OCTAL_PSRAM/37_37") (pintype "bidirectional"))
    )
    (net (code "101") (name "unconnected-(J9-PadRSET)") (class "Default")
      (node (ref "J9") (pin "RSET") (pinfunction "RSET_RSET") (pintype "bidirectional"))
    )
    (net (code "102") (name "unconnected-(J9-RGB_LED{slash}48-Pad48)") (class "Default")
      (node (ref "J9") (pin "48") (pinfunction "RGB_LED/48_48") (pintype "bidirectional"))
    )
    (net (code "103") (name "unconnected-(J9-SPI_VOLT{slash}45-Pad45)") (class "Default")
      (node (ref "J9") (pin "45") (pinfunction "SPI_VOLT/45_45") (pintype "bidirectional"))
    )
    (net (code "104") (name "unconnected-(J9-U0RX{slash}44-PadRX)") (class "Default")
      (node (ref "J9") (pin "RX") (pinfunction "U0RX/44_RX") (pintype "bidirectional"))
    )
    (net (code "105") (name "unconnected-(J9-U0TXD{slash}43-PadTX)") (class "Default")
      (node (ref "J9") (pin "TX") (pinfunction "U0TXD/43_TX") (pintype "bidirectional"))
    )
    (net (code "106") (name "unconnected-(J10-KEY-Pad7)") (class "Default")
      (node (ref "J10") (pin "7") (pinfunction "KEY_7") (pintype "bidirectional"))
    )
    (net (code "107") (name "unconnected-(J10-~{RESET}-Pad10)") (class "Default")
      (node (ref "J10") (pin "10") (pinfunction "~{RESET}_10") (pintype "bidirectional"))
    )
    (net (code "108") (name "unconnected-(J13-1-Pad3V3)") (class "Default")
      (node (ref "J13") (pin "3V3") (pinfunction "1_3V3") (pintype "passive"))
    )
    (net (code "109") (name "unconnected-(J13-2-PadCLK)") (class "Default")
      (node (ref "J13") (pin "CLK") (pinfunction "2_CLK") (pintype "passive"))
    )
    (net (code "110") (name "unconnected-(J13-3-PadCS)") (class "Default")
      (node (ref "J13") (pin "CS") (pinfunction "3_CS") (pintype "passive"))
    )
    (net (code "111") (name "unconnected-(J13-4-PadGND)") (class "Default")
      (node (ref "J13") (pin "GND") (pinfunction "4_GND") (pintype "passive"))
    )
    (net (code "112") (name "unconnected-(J13-5-PadMISO)") (class "Default")
      (node (ref "J13") (pin "MISO") (pinfunction "5_MISO") (pintype "passive"))
    )
    (net (code "113") (name "unconnected-(J13-6-PadMOSI)") (class "Default")
      (node (ref "J13") (pin "MOSI") (pinfunction "6_MOSI") (pintype "passive"))
    )
    (net (code "114") (name "unconnected-(J13-7-PadRSET)") (class "Default")
      (node (ref "J13") (pin "RSET") (pinfunction "7_RSET") (pintype "passive"))
    )
    (net (code "115") (name "unconnected-(J13-8-PadRXD)") (class "Default")
      (node (ref "J13") (pin "RXD") (pinfunction "8_RXD") (pintype "passive"))
    )
    (net (code "116") (name "unconnected-(J13-9-PadTEST)") (class "Default")
      (node (ref "J13") (pin "TEST") (pinfunction "9_TEST") (pintype "passive"))
    )
    (net (code "117") (name "unconnected-(J13-10-PadTXD)") (class "Default")
      (node (ref "J13") (pin "TXD") (pinfunction "10_TXD") (pintype "passive"))
    )
    (net (code "118") (name "unconnected-(J14-1-PadVCC)") (class "Default")
      (node (ref "J14") (pin "VCC") (pinfunction "1_VCC") (pintype "passive"))
    )
    (net (code "119") (name "unconnected-(J14-2-PadCLK)") (class "Default")
      (node (ref "J14") (pin "CLK") (pinfunction "2_CLK") (pintype "passive"))
    )
    (net (code "120") (name "unconnected-(J14-3-Pad_CS)") (class "Default")
      (node (ref "J14") (pin "_CS") (pinfunction "3__CS") (pintype "passive"))
    )
    (net (code "121") (name "unconnected-(J14-4-PadGND)") (class "Default")
      (node (ref "J14") (pin "GND") (pinfunction "4_GND") (pintype "passive"))
    )
    (net (code "122") (name "unconnected-(J14-5-PadMISO)") (class "Default")
      (node (ref "J14") (pin "MISO") (pinfunction "5_MISO") (pintype "passive"))
    )
    (net (code "123") (name "unconnected-(J14-6-PadMOSI)") (class "Default")
      (node (ref "J14") (pin "MOSI") (pinfunction "6_MOSI") (pintype "passive"))
    )
    (net (code "124") (name "unconnected-(J14-7-PadRSET)") (class "Default")
      (node (ref "J14") (pin "RSET") (pinfunction "7_RSET") (pintype "passive"))
    )
    (net (code "125") (name "unconnected-(J14-8-PadRXD)") (class "Default")
      (node (ref "J14") (pin "RXD") (pinfunction "8_RXD") (pintype "passive"))
    )
    (net (code "126") (name "unconnected-(J14-9-PadTEST)") (class "Default")
      (node (ref "J14") (pin "TEST") (pinfunction "9_TEST") (pintype "passive"))
    )
    (net (code "127") (name "unconnected-(J14-10-PadTXD)") (class "Default")
      (node (ref "J14") (pin "TXD") (pinfunction "10_TXD") (pintype "passive"))
    )
    (net (code "128") (name "unconnected-(J15-1-PadVCC)") (class "Default")
      (node (ref "J15") (pin "VCC") (pinfunction "1_VCC") (pintype "passive"))
    )
    (net (code "129") (name "unconnected-(J15-2-PadCLK)") (class "Default")
      (node (ref "J15") (pin "CLK") (pinfunction "2_CLK") (pintype "passive"))
    )
    (net (code "130") (name "unconnected-(J15-3-Pad_CS)") (class "Default")
      (node (ref "J15") (pin "_CS") (pinfunction "3__CS") (pintype "passive"))
    )
    (net (code "131") (name "unconnected-(J15-4-PadGND)") (class "Default")
      (node (ref "J15") (pin "GND") (pinfunction "4_GND") (pintype "passive"))
    )
    (net (code "132") (name "unconnected-(J15-5-PadMISO)") (class "Default")
      (node (ref "J15") (pin "MISO") (pinfunction "5_MISO") (pintype "passive"))
    )
    (net (code "133") (name "unconnected-(J15-6-PadMOSI)") (class "Default")
      (node (ref "J15") (pin "MOSI") (pinfunction "6_MOSI") (pintype "passive"))
    )
    (net (code "134") (name "unconnected-(J15-7-PadRSET)") (class "Default")
      (node (ref "J15") (pin "RSET") (pinfunction "7_RSET") (pintype "passive"))
    )
    (net (code "135") (name "unconnected-(J15-8-PadRXD)") (class "Default")
      (node (ref "J15") (pin "RXD") (pinfunction "8_RXD") (pintype "passive"))
    )
    (net (code "136") (name "unconnected-(J15-9-PadTEST)") (class "Default")
      (node (ref "J15") (pin "TEST") (pinfunction "9_TEST") (pintype "passive"))
    )
    (net (code "137") (name "unconnected-(J15-10-PadTXD)") (class "Default")
      (node (ref "J15") (pin "TXD") (pinfunction "10_TXD") (pintype "passive"))
    )
    (net (code "138") (name "unconnected-(J16-1-Pad3V3)") (class "Default")
      (node (ref "J16") (pin "3V3") (pinfunction "1_3V3") (pintype "passive"))
    )
    (net (code "139") (name "unconnected-(J16-2-PadCLK)") (class "Default")
      (node (ref "J16") (pin "CLK") (pinfunction "2_CLK") (pintype "passive"))
    )
    (net (code "140") (name "unconnected-(J16-3-PadCS)") (class "Default")
      (node (ref "J16") (pin "CS") (pinfunction "3_CS") (pintype "passive"))
    )
    (net (code "141") (name "unconnected-(J16-4-PadGND)") (class "Default")
      (node (ref "J16") (pin "GND") (pinfunction "4_GND") (pintype "passive"))
    )
    (net (code "142") (name "unconnected-(J16-5-PadMISO)") (class "Default")
      (node (ref "J16") (pin "MISO") (pinfunction "5_MISO") (pintype "passive"))
    )
    (net (code "143") (name "unconnected-(J16-6-PadMOSI)") (class "Default")
      (node (ref "J16") (pin "MOSI") (pinfunction "6_MOSI") (pintype "passive"))
    )
    (net (code "144") (name "unconnected-(J16-7-PadRSET)") (class "Default")
      (node (ref "J16") (pin "RSET") (pinfunction "7_RSET") (pintype "passive"))
    )
    (net (code "145") (name "unconnected-(J16-8-PadRXD)") (class "Default")
      (node (ref "J16") (pin "RXD") (pinfunction "8_RXD") (pintype "passive"))
    )
    (net (code "146") (name "unconnected-(J16-9-PadTEST)") (class "Default")
      (node (ref "J16") (pin "TEST") (pinfunction "9_TEST") (pintype "passive"))
    )
    (net (code "147") (name "unconnected-(J16-10-PadTXD)") (class "Default")
      (node (ref "J16") (pin "TXD") (pinfunction "10_TXD") (pintype "passive"))
    )
    (net (code "148") (name "unconnected-(J17-1-PadVCC)") (class "Default")
      (node (ref "J17") (pin "VCC") (pinfunction "1_VCC") (pintype "passive"))
    )
    (net (code "149") (name "unconnected-(J17-2-PadCLK)") (class "Default")
      (node (ref "J17") (pin "CLK") (pinfunction "2_CLK") (pintype "passive"))
    )
    (net (code "150") (name "unconnected-(J17-3-Pad_CS)") (class "Default")
      (node (ref "J17") (pin "_CS") (pinfunction "3__CS") (pintype "passive"))
    )
    (net (code "151") (name "unconnected-(J17-4-PadGND)") (class "Default")
      (node (ref "J17") (pin "GND") (pinfunction "4_GND") (pintype "passive"))
    )
    (net (code "152") (name "unconnected-(J17-5-PadMISO)") (class "Default")
      (node (ref "J17") (pin "MISO") (pinfunction "5_MISO") (pintype "passive"))
    )
    (net (code "153") (name "unconnected-(J17-6-PadMOSI)") (class "Default")
      (node (ref "J17") (pin "MOSI") (pinfunction "6_MOSI") (pintype "passive"))
    )
    (net (code "154") (name "unconnected-(J17-7-PadRSET)") (class "Default")
      (node (ref "J17") (pin "RSET") (pinfunction "7_RSET") (pintype "passive"))
    )
    (net (code "155") (name "unconnected-(J17-8-PadRXD)") (class "Default")
      (node (ref "J17") (pin "RXD") (pinfunction "8_RXD") (pintype "passive"))
    )
    (net (code "156") (name "unconnected-(J17-9-PadTEST)") (class "Default")
      (node (ref "J17") (pin "TEST") (pinfunction "9_TEST") (pintype "passive"))
    )
    (net (code "157") (name "unconnected-(J17-10-PadTXD)") (class "Default")
      (node (ref "J17") (pin "TXD") (pinfunction "10_TXD") (pintype "passive"))
    )
    (net (code "158") (name "unconnected-(J18-1-Pad3V3)") (class "Default")
      (node (ref "J18") (pin "3V3") (pinfunction "1_3V3") (pintype "passive"))
    )
    (net (code "159") (name "unconnected-(J18-2-PadCLK)") (class "Default")
      (node (ref "J18") (pin "CLK") (pinfunction "2_CLK") (pintype "passive"))
    )
    (net (code "160") (name "unconnected-(J18-3-PadCS)") (class "Default")
      (node (ref "J18") (pin "CS") (pinfunction "3_CS") (pintype "passive"))
    )
    (net (code "161") (name "unconnected-(J18-4-PadGND)") (class "Default")
      (node (ref "J18") (pin "GND") (pinfunction "4_GND") (pintype "passive"))
    )
    (net (code "162") (name "unconnected-(J18-5-PadMISO)") (class "Default")
      (node (ref "J18") (pin "MISO") (pinfunction "5_MISO") (pintype "passive"))
    )
    (net (code "163") (name "unconnected-(J18-6-PadMOSI)") (class "Default")
      (node (ref "J18") (pin "MOSI") (pinfunction "6_MOSI") (pintype "passive"))
    )
    (net (code "164") (name "unconnected-(J18-7-PadRSET)") (class "Default")
      (node (ref "J18") (pin "RSET") (pinfunction "7_RSET") (pintype "passive"))
    )
    (net (code "165") (name "unconnected-(J18-8-PadRXD)") (class "Default")
      (node (ref "J18") (pin "RXD") (pinfunction "8_RXD") (pintype "passive"))
    )
    (net (code "166") (name "unconnected-(J18-9-PadTEST)") (class "Default")
      (node (ref "J18") (pin "TEST") (pinfunction "9_TEST") (pintype "passive"))
    )
    (net (code "167") (name "unconnected-(J18-10-PadTXD)") (class "Default")
      (node (ref "J18") (pin "TXD") (pinfunction "10_TXD") (pintype "passive"))
    )
    (net (code "168") (name "unconnected-(J19-1-Pad3V3)") (class "Default")
      (node (ref "J19") (pin "3V3") (pinfunction "1_3V3") (pintype "passive"))
    )
    (net (code "169") (name "unconnected-(J19-2-PadCLK)") (class "Default")
      (node (ref "J19") (pin "CLK") (pinfunction "2_CLK") (pintype "passive"))
    )
    (net (code "170") (name "unconnected-(J19-3-PadCS)") (class "Default")
      (node (ref "J19") (pin "CS") (pinfunction "3_CS") (pintype "passive"))
    )
    (net (code "171") (name "unconnected-(J19-4-PadGND)") (class "Default")
      (node (ref "J19") (pin "GND") (pinfunction "4_GND") (pintype "passive"))
    )
    (net (code "172") (name "unconnected-(J19-5-PadMISO)") (class "Default")
      (node (ref "J19") (pin "MISO") (pinfunction "5_MISO") (pintype "passive"))
    )
    (net (code "173") (name "unconnected-(J19-6-PadMOSI)") (class "Default")
      (node (ref "J19") (pin "MOSI") (pinfunction "6_MOSI") (pintype "passive"))
    )
    (net (code "174") (name "unconnected-(J19-7-PadRSET)") (class "Default")
      (node (ref "J19") (pin "RSET") (pinfunction "7_RSET") (pintype "passive"))
    )
    (net (code "175") (name "unconnected-(J19-8-PadRXD)") (class "Default")
      (node (ref "J19") (pin "RXD") (pinfunction "8_RXD") (pintype "passive"))
    )
    (net (code "176") (name "unconnected-(J19-9-PadTEST)") (class "Default")
      (node (ref "J19") (pin "TEST") (pinfunction "9_TEST") (pintype "passive"))
    )
    (net (code "177") (name "unconnected-(J19-10-PadTXD)") (class "Default")
      (node (ref "J19") (pin "TXD") (pinfunction "10_TXD") (pintype "passive"))
    )
    (net (code "178") (name "unconnected-(J20-1-PadVCC)") (class "Default")
      (node (ref "J20") (pin "VCC") (pinfunction "1_VCC") (pintype "passive"))
    )
    (net (code "179") (name "unconnected-(J20-2-PadCLK)") (class "Default")
      (node (ref "J20") (pin "CLK") (pinfunction "2_CLK") (pintype "passive"))
    )
    (net (code "180") (name "unconnected-(J20-3-Pad_CS)") (class "Default")
      (node (ref "J20") (pin "_CS") (pinfunction "3__CS") (pintype "passive"))
    )
    (net (code "181") (name "unconnected-(J20-4-PadGND)") (class "Default")
      (node (ref "J20") (pin "GND") (pinfunction "4_GND") (pintype "passive"))
    )
    (net (code "182") (name "unconnected-(J20-5-PadMISO)") (class "Default")
      (node (ref "J20") (pin "MISO") (pinfunction "5_MISO") (pintype "passive"))
    )
    (net (code "183") (name "unconnected-(J20-6-PadMOSI)") (class "Default")
      (node (ref "J20") (pin "MOSI") (pinfunction "6_MOSI") (pintype "passive"))
    )
    (net (code "184") (name "unconnected-(J20-7-PadRSET)") (class "Default")
      (node (ref "J20") (pin "RSET") (pinfunction "7_RSET") (pintype "passive"))
    )
    (net (code "185") (name "unconnected-(J20-8-PadRXD)") (class "Default")
      (node (ref "J20") (pin "RXD") (pinfunction "8_RXD") (pintype "passive"))
    )
    (net (code "186") (name "unconnected-(J20-9-PadTEST)") (class "Default")
      (node (ref "J20") (pin "TEST") (pinfunction "9_TEST") (pintype "passive"))
    )
    (net (code "187") (name "unconnected-(J20-10-PadTXD)") (class "Default")
      (node (ref "J20") (pin "TXD") (pinfunction "10_TXD") (pintype "passive"))
    )
  )
)
